# LedTester.net
KiCad netlist of a schematic drawn in EAGLE
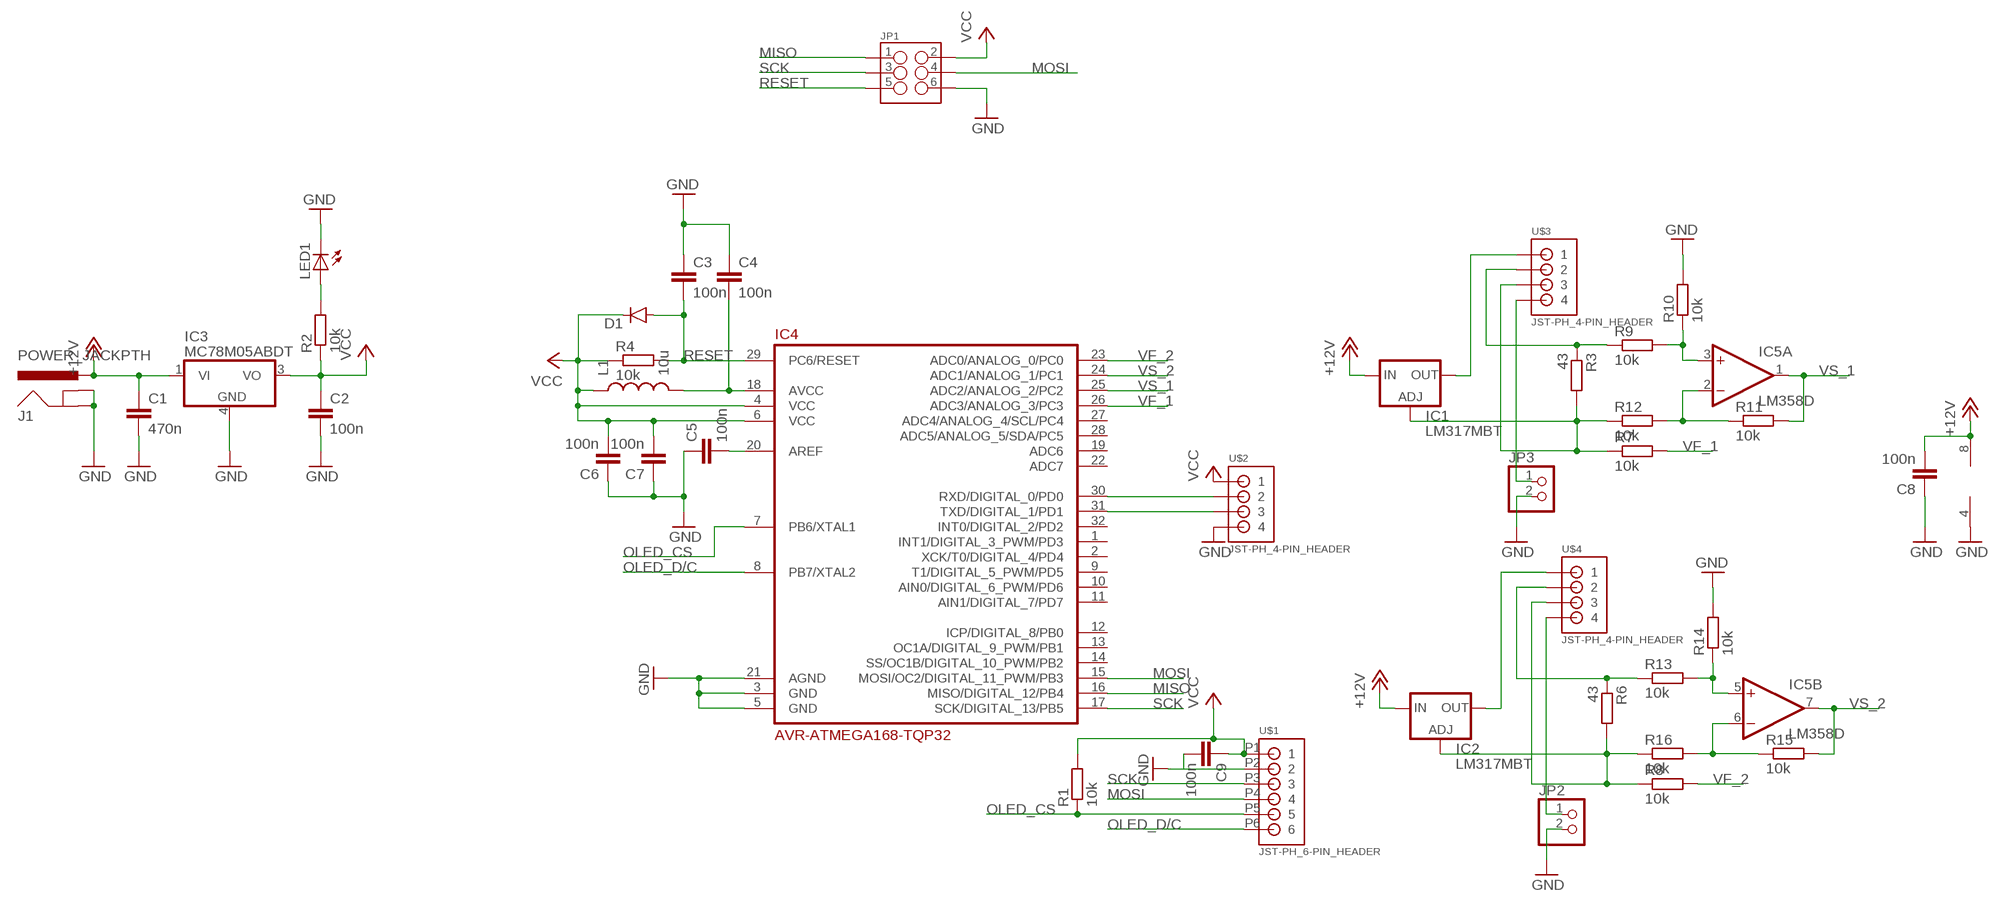
[diagram p0: schematic, sheet 1]

(export (version "E")
  (design (tool "Eeschema 10.0.6"))
  (components
    (comp (ref "C1")
      (value "470n")
      (footprint "eagle-import:C0603")
      (libsource (lib "eagle-import") (part "C-EUC0603"))
    )
    (comp (ref "C2")
      (value "100n")
      (footprint "eagle-import:C0603")
      (libsource (lib "eagle-import") (part "C-EUC0603"))
    )
    (comp (ref "C3")
      (value "100n")
      (footprint "eagle-import:C0603")
      (libsource (lib "eagle-import") (part "C-EUC0603"))
    )
    (comp (ref "C4")
      (value "100n")
      (footprint "eagle-import:C0603")
      (libsource (lib "eagle-import") (part "C-EUC0603"))
    )
    (comp (ref "C5")
      (value "100n")
      (footprint "eagle-import:C0603")
      (libsource (lib "eagle-import") (part "C-EUC0603"))
    )
    (comp (ref "C6")
      (value "100n")
      (footprint "eagle-import:C0603")
      (libsource (lib "eagle-import") (part "C-EUC0603"))
    )
    (comp (ref "C7")
      (value "100n")
      (footprint "eagle-import:C0603")
      (libsource (lib "eagle-import") (part "C-EUC0603"))
    )
    (comp (ref "C8")
      (value "100n")
      (footprint "eagle-import:C0603")
      (libsource (lib "eagle-import") (part "C-EUC0603"))
    )
    (comp (ref "C9")
      (value "100n")
      (footprint "eagle-import:C0603")
      (libsource (lib "eagle-import") (part "C-EUC0603"))
    )
    (comp (ref "D1")
      (value "DIODESOD")
      (footprint "eagle-import:SOD-323")
      (libsource (lib "eagle-import") (part "DIODESOD"))
    )
    (comp (ref "IC1")
      (value "LM317MBT")
      (footprint "eagle-import:TO220L1")
      (libsource (lib "eagle-import") (part "LM317?MBT"))
    )
    (comp (ref "IC2")
      (value "LM317MBT")
      (footprint "eagle-import:TO220L1")
      (libsource (lib "eagle-import") (part "LM317?MBT"))
    )
    (comp (ref "IC3")
      (value "MC78M05ABDT")
      (footprint "eagle-import:DPACK_3")
      (libsource (lib "eagle-import") (part "MC78M05ABDT"))
    )
    (comp (ref "IC4")
      (value "AVR-ATMEGA168-TQP32")
      (footprint "eagle-import:QFP32")
      (libsource (lib "eagle-import") (part "AVR-ATMEGA168-TQP32"))
    )
    (comp (ref "IC5")
      (value "LM358D")
      (footprint "eagle-import:SO08")
      (libsource (lib "eagle-import") (part "LM358D"))
    )
    (comp (ref "J1")
      (value "POWER_JACKPTH")
      (footprint "eagle-import:POWER_JACK_PTH")
      (libsource (lib "eagle-import") (part "POWER_JACKPTH"))
    )
    (comp (ref "JP1")
      (value "M03X2SHROUD")
      (footprint "eagle-import:2X3-SHROUDED")
      (libsource (lib "eagle-import") (part "M03X2SHROUD"))
    )
    (comp (ref "JP2")
      (value "PINHD-1X2")
      (footprint "eagle-import:1X02")
      (libsource (lib "eagle-import") (part "PINHD-1X2"))
    )
    (comp (ref "JP3")
      (value "PINHD-1X2")
      (footprint "eagle-import:1X02")
      (libsource (lib "eagle-import") (part "PINHD-1X2"))
    )
    (comp (ref "L1")
      (value "10u")
      (footprint "eagle-import:0603")
      (libsource (lib "eagle-import") (part "INDUCTOR0603"))
    )
    (comp (ref "LED1")
      (value "LEDCHIP-LED0603")
      (footprint "eagle-import:CHIP-LED0603")
      (libsource (lib "eagle-import") (part "LEDCHIP-LED0603"))
    )
    (comp (ref "R1")
      (value "10k")
      (footprint "eagle-import:R0603")
      (libsource (lib "eagle-import") (part "R-EU_R0603"))
    )
    (comp (ref "R2")
      (value "10k")
      (footprint "eagle-import:R0603")
      (libsource (lib "eagle-import") (part "R-EU_R0603"))
    )
    (comp (ref "R3")
      (value "43")
      (footprint "eagle-import:R0603")
      (libsource (lib "eagle-import") (part "R-EU_R0603"))
    )
    (comp (ref "R4")
      (value "10k")
      (footprint "eagle-import:R0603")
      (libsource (lib "eagle-import") (part "R-EU_R0603"))
    )
    (comp (ref "R6")
      (value "43")
      (footprint "eagle-import:R0603")
      (libsource (lib "eagle-import") (part "R-EU_R0603"))
    )
    (comp (ref "R7")
      (value "10k")
      (footprint "eagle-import:R0603")
      (libsource (lib "eagle-import") (part "R-EU_R0603"))
    )
    (comp (ref "R8")
      (value "10k")
      (footprint "eagle-import:R0603")
      (libsource (lib "eagle-import") (part "R-EU_R0603"))
    )
    (comp (ref "R9")
      (value "10k")
      (footprint "eagle-import:R0603")
      (libsource (lib "eagle-import") (part "R-EU_R0603"))
    )
    (comp (ref "R10")
      (value "10k")
      (footprint "eagle-import:R0603")
      (libsource (lib "eagle-import") (part "R-EU_R0603"))
    )
    (comp (ref "R11")
      (value "10k")
      (footprint "eagle-import:R0603")
      (libsource (lib "eagle-import") (part "R-EU_R0603"))
    )
    (comp (ref "R12")
      (value "10k")
      (footprint "eagle-import:R0603")
      (libsource (lib "eagle-import") (part "R-EU_R0603"))
    )
    (comp (ref "R13")
      (value "10k")
      (footprint "eagle-import:R0603")
      (libsource (lib "eagle-import") (part "R-EU_R0603"))
    )
    (comp (ref "R14")
      (value "10k")
      (footprint "eagle-import:R0603")
      (libsource (lib "eagle-import") (part "R-EU_R0603"))
    )
    (comp (ref "R15")
      (value "10k")
      (footprint "eagle-import:R0603")
      (libsource (lib "eagle-import") (part "R-EU_R0603"))
    )
    (comp (ref "R16")
      (value "10k")
      (footprint "eagle-import:R0603")
      (libsource (lib "eagle-import") (part "R-EU_R0603"))
    )
    (comp (ref "U$1")
      (value "JST-PH_6-PIN_HEADER")
      (footprint "eagle-import:JST_B6B-PH_HEADER")
      (libsource (lib "eagle-import") (part "JST-PH_6-PIN_HEADER"))
    )
    (comp (ref "U$2")
      (value "JST-PH_4-PIN_HEADER")
      (footprint "eagle-import:JST_B4B-PH_HEADER")
      (libsource (lib "eagle-import") (part "JST-PH_4-PIN_HEADER"))
    )
    (comp (ref "U$3")
      (value "JST-PH_4-PIN_HEADER")
      (footprint "eagle-import:JST_B4B-PH_HEADER")
      (libsource (lib "eagle-import") (part "JST-PH_4-PIN_HEADER"))
    )
    (comp (ref "U$4")
      (value "JST-PH_4-PIN_HEADER")
      (footprint "eagle-import:JST_B4B-PH_HEADER")
      (libsource (lib "eagle-import") (part "JST-PH_4-PIN_HEADER"))
    )
  )
  (nets
    (net (code "1") (name "+12V") (class "Default")
      (node (ref "C1") (pin "1") (pinfunction "1_1") (pintype "passive"))
      (node (ref "C8") (pin "2") (pinfunction "2_2") (pintype "passive"))
      (node (ref "IC1") (pin "3") (pinfunction "IN_3") (pintype "input"))
      (node (ref "IC2") (pin "3") (pinfunction "IN_3") (pintype "input"))
      (node (ref "IC3") (pin "1") (pinfunction "VI_1") (pintype "input"))
      (node (ref "IC5") (pin "8") (pinfunction "V+_8") (pintype "power_in"))
      (node (ref "J1") (pin "PWR") (pinfunction "PWR_PWR") (pintype "bidirectional"))
    )
    (net (code "2") (name "/MISO") (class "Default")
      (node (ref "IC4") (pin "16") (pinfunction "MISO/DIGITAL_12/PB4_16") (pintype "bidirectional"))
      (node (ref "JP1") (pin "1") (pinfunction "1_1") (pintype "bidirectional"))
    )
    (net (code "3") (name "/MOSI") (class "Default")
      (node (ref "IC4") (pin "15") (pinfunction "MOSI/OC2/DIGITAL_11_PWM/PB3_15") (pintype "bidirectional"))
      (node (ref "JP1") (pin "4") (pinfunction "4_4") (pintype "bidirectional"))
      (node (ref "U$1") (pin "P4") (pinfunction "4_P4") (pintype "bidirectional"))
    )
    (net (code "4") (name "/OLED_CS") (class "Default")
      (node (ref "IC4") (pin "7") (pinfunction "PB6/XTAL1_7") (pintype "bidirectional"))
      (node (ref "R1") (pin "1") (pinfunction "1_1") (pintype "passive"))
      (node (ref "U$1") (pin "P5") (pinfunction "5_P5") (pintype "bidirectional"))
    )
    (net (code "5") (name "/OLED_D{slash}C") (class "Default")
      (node (ref "IC4") (pin "8") (pinfunction "PB7/XTAL2_8") (pintype "bidirectional"))
      (node (ref "U$1") (pin "P6") (pinfunction "6_P6") (pintype "bidirectional"))
    )
    (net (code "6") (name "/RESET") (class "Default")
      (node (ref "C3") (pin "2") (pinfunction "2_2") (pintype "passive"))
      (node (ref "D1") (pin "A") (pinfunction "A_A") (pintype "passive"))
      (node (ref "IC4") (pin "29") (pinfunction "PC6/RESET_29") (pintype "bidirectional"))
      (node (ref "JP1") (pin "5") (pinfunction "5_5") (pintype "bidirectional"))
      (node (ref "R4") (pin "2") (pinfunction "2_2") (pintype "passive"))
    )
    (net (code "7") (name "/SCK") (class "Default")
      (node (ref "IC4") (pin "17") (pinfunction "SCK/DIGITAL_13/PB5_17") (pintype "bidirectional"))
      (node (ref "JP1") (pin "3") (pinfunction "3_3") (pintype "bidirectional"))
      (node (ref "U$1") (pin "P3") (pinfunction "3_P3") (pintype "bidirectional"))
    )
    (net (code "8") (name "/VF_1") (class "Default")
      (node (ref "IC4") (pin "26") (pinfunction "ADC3/ANALOG_3/PC3_26") (pintype "bidirectional"))
      (node (ref "R7") (pin "2") (pinfunction "2_2") (pintype "passive"))
    )
    (net (code "9") (name "/VF_2") (class "Default")
      (node (ref "IC4") (pin "23") (pinfunction "ADC0/ANALOG_0/PC0_23") (pintype "bidirectional"))
      (node (ref "R8") (pin "2") (pinfunction "2_2") (pintype "passive"))
    )
    (net (code "10") (name "/VS_1") (class "Default")
      (node (ref "IC4") (pin "25") (pinfunction "ADC2/ANALOG_2/PC2_25") (pintype "bidirectional"))
      (node (ref "IC5") (pin "1") (pinfunction "OUT_1") (pintype "output"))
      (node (ref "R11") (pin "2") (pinfunction "2_2") (pintype "passive"))
    )
    (net (code "11") (name "/VS_2") (class "Default")
      (node (ref "IC4") (pin "24") (pinfunction "ADC1/ANALOG_1/PC1_24") (pintype "bidirectional"))
      (node (ref "IC5") (pin "7") (pinfunction "OUT_7") (pintype "output"))
      (node (ref "R15") (pin "2") (pinfunction "2_2") (pintype "passive"))
    )
    (net (code "12") (name "GND") (class "Default")
      (node (ref "C1") (pin "2") (pinfunction "2_2") (pintype "passive"))
      (node (ref "C2") (pin "2") (pinfunction "2_2") (pintype "passive"))
      (node (ref "C3") (pin "1") (pinfunction "1_1") (pintype "passive"))
      (node (ref "C4") (pin "1") (pinfunction "1_1") (pintype "passive"))
      (node (ref "C5") (pin "1") (pinfunction "1_1") (pintype "passive"))
      (node (ref "C6") (pin "1") (pinfunction "1_1") (pintype "passive"))
      (node (ref "C7") (pin "1") (pinfunction "1_1") (pintype "passive"))
      (node (ref "C8") (pin "1") (pinfunction "1_1") (pintype "passive"))
      (node (ref "C9") (pin "2") (pinfunction "2_2") (pintype "passive"))
      (node (ref "IC3") (pin "4") (pinfunction "GND_4") (pintype "passive"))
      (node (ref "IC4") (pin "21") (pinfunction "AGND_21") (pintype "power_in"))
      (node (ref "IC4") (pin "3") (pinfunction "GND_3") (pintype "power_in"))
      (node (ref "IC4") (pin "5") (pinfunction "GND_5") (pintype "power_in"))
      (node (ref "IC5") (pin "4") (pinfunction "V-_4") (pintype "power_in"))
      (node (ref "J1") (pin "GND") (pinfunction "GND_GND") (pintype "bidirectional"))
      (node (ref "J1") (pin "GNDBREAK") (pinfunction "GNDBREAK_GNDBREAK") (pintype "bidirectional"))
      (node (ref "JP1") (pin "6") (pinfunction "6_6") (pintype "bidirectional"))
      (node (ref "JP2") (pin "2") (pinfunction "2_2") (pintype "passive"))
      (node (ref "JP3") (pin "2") (pinfunction "2_2") (pintype "passive"))
      (node (ref "LED1") (pin "C") (pinfunction "C_C") (pintype "passive"))
      (node (ref "R10") (pin "2") (pinfunction "2_2") (pintype "passive"))
      (node (ref "R14") (pin "2") (pinfunction "2_2") (pintype "passive"))
      (node (ref "U$1") (pin "P2") (pinfunction "2_P2") (pintype "bidirectional"))
      (node (ref "U$2") (pin "P4") (pinfunction "4_P4") (pintype "bidirectional"))
    )
    (net (code "13") (name "Net-(IC1-ADJ)") (class "Default")
      (node (ref "IC1") (pin "1") (pinfunction "ADJ_1") (pintype "input"))
      (node (ref "R12") (pin "1") (pinfunction "1_1") (pintype "passive"))
      (node (ref "R3") (pin "2") (pinfunction "2_2") (pintype "passive"))
      (node (ref "R7") (pin "1") (pinfunction "1_1") (pintype "passive"))
      (node (ref "U$3") (pin "P3") (pinfunction "3_P3") (pintype "bidirectional"))
    )
    (net (code "14") (name "Net-(IC1-OUT)") (class "Default")
      (node (ref "IC1") (pin "2") (pinfunction "OUT_2") (pintype "passive"))
      (node (ref "U$3") (pin "P1") (pinfunction "1_P1") (pintype "bidirectional"))
    )
    (net (code "15") (name "Net-(IC2-ADJ)") (class "Default")
      (node (ref "IC2") (pin "1") (pinfunction "ADJ_1") (pintype "input"))
      (node (ref "R16") (pin "1") (pinfunction "1_1") (pintype "passive"))
      (node (ref "R6") (pin "2") (pinfunction "2_2") (pintype "passive"))
      (node (ref "R8") (pin "1") (pinfunction "1_1") (pintype "passive"))
      (node (ref "U$4") (pin "P3") (pinfunction "3_P3") (pintype "bidirectional"))
    )
    (net (code "16") (name "Net-(IC2-OUT)") (class "Default")
      (node (ref "IC2") (pin "2") (pinfunction "OUT_2") (pintype "passive"))
      (node (ref "U$4") (pin "P1") (pinfunction "1_P1") (pintype "bidirectional"))
    )
    (net (code "17") (name "Net-(IC4-AREF)") (class "Default")
      (node (ref "C5") (pin "2") (pinfunction "2_2") (pintype "passive"))
      (node (ref "IC4") (pin "20") (pinfunction "AREF_20") (pintype "bidirectional"))
    )
    (net (code "18") (name "Net-(IC4-AVCC)") (class "Default")
      (node (ref "C4") (pin "2") (pinfunction "2_2") (pintype "passive"))
      (node (ref "IC4") (pin "18") (pinfunction "AVCC_18") (pintype "power_in"))
      (node (ref "L1") (pin "2") (pinfunction "2_2") (pintype "passive"))
    )
    (net (code "19") (name "Net-(IC4-RXD{slash}DIGITAL_0{slash}PD0)") (class "Default")
      (node (ref "IC4") (pin "30") (pinfunction "RXD/DIGITAL_0/PD0_30") (pintype "bidirectional"))
      (node (ref "U$2") (pin "P2") (pinfunction "2_P2") (pintype "bidirectional"))
    )
    (net (code "20") (name "Net-(IC4-TXD{slash}DIGITAL_1{slash}PD1)") (class "Default")
      (node (ref "IC4") (pin "31") (pinfunction "TXD/DIGITAL_1/PD1_31") (pintype "bidirectional"))
      (node (ref "U$2") (pin "P3") (pinfunction "3_P3") (pintype "bidirectional"))
    )
    (net (code "21") (name "Net-(IC5A-+IN)") (class "Default")
      (node (ref "IC5") (pin "3") (pinfunction "+IN_3") (pintype "input"))
      (node (ref "R10") (pin "1") (pinfunction "1_1") (pintype "passive"))
      (node (ref "R9") (pin "2") (pinfunction "2_2") (pintype "passive"))
    )
    (net (code "22") (name "Net-(IC5A--IN)") (class "Default")
      (node (ref "IC5") (pin "2") (pinfunction "-IN_2") (pintype "input"))
      (node (ref "R11") (pin "1") (pinfunction "1_1") (pintype "passive"))
      (node (ref "R12") (pin "2") (pinfunction "2_2") (pintype "passive"))
    )
    (net (code "23") (name "Net-(IC5B-+IN)") (class "Default")
      (node (ref "IC5") (pin "5") (pinfunction "+IN_5") (pintype "input"))
      (node (ref "R13") (pin "2") (pinfunction "2_2") (pintype "passive"))
      (node (ref "R14") (pin "1") (pinfunction "1_1") (pintype "passive"))
    )
    (net (code "24") (name "Net-(IC5B--IN)") (class "Default")
      (node (ref "IC5") (pin "6") (pinfunction "-IN_6") (pintype "input"))
      (node (ref "R15") (pin "1") (pinfunction "1_1") (pintype "passive"))
      (node (ref "R16") (pin "2") (pinfunction "2_2") (pintype "passive"))
    )
    (net (code "25") (name "Net-(LED1-PadA)") (class "Default")
      (node (ref "LED1") (pin "A") (pinfunction "A_A") (pintype "passive"))
      (node (ref "R2") (pin "2") (pinfunction "2_2") (pintype "passive"))
    )
    (net (code "26") (name "Net-(U$3-2)") (class "Default")
      (node (ref "R3") (pin "1") (pinfunction "1_1") (pintype "passive"))
      (node (ref "R9") (pin "1") (pinfunction "1_1") (pintype "passive"))
      (node (ref "U$3") (pin "P2") (pinfunction "2_P2") (pintype "bidirectional"))
    )
    (net (code "27") (name "Net-(U$3-4)") (class "Default")
      (node (ref "JP3") (pin "1") (pinfunction "1_1") (pintype "passive"))
      (node (ref "U$3") (pin "P4") (pinfunction "4_P4") (pintype "bidirectional"))
    )
    (net (code "28") (name "Net-(U$4-2)") (class "Default")
      (node (ref "R13") (pin "1") (pinfunction "1_1") (pintype "passive"))
      (node (ref "R6") (pin "1") (pinfunction "1_1") (pintype "passive"))
      (node (ref "U$4") (pin "P2") (pinfunction "2_P2") (pintype "bidirectional"))
    )
    (net (code "29") (name "Net-(U$4-4)") (class "Default")
      (node (ref "JP2") (pin "1") (pinfunction "1_1") (pintype "passive"))
      (node (ref "U$4") (pin "P4") (pinfunction "4_P4") (pintype "bidirectional"))
    )
    (net (code "30") (name "VCC") (class "Default")
      (node (ref "C2") (pin "1") (pinfunction "1_1") (pintype "passive"))
      (node (ref "C6") (pin "2") (pinfunction "2_2") (pintype "passive"))
      (node (ref "C7") (pin "2") (pinfunction "2_2") (pintype "passive"))
      (node (ref "C9") (pin "1") (pinfunction "1_1") (pintype "passive"))
      (node (ref "D1") (pin "C") (pinfunction "C_C") (pintype "passive"))
      (node (ref "IC3") (pin "3") (pinfunction "VO_3") (pintype "passive"))
      (node (ref "IC4") (pin "4") (pinfunction "VCC_4") (pintype "power_in"))
      (node (ref "IC4") (pin "6") (pinfunction "VCC_6") (pintype "power_in"))
      (node (ref "JP1") (pin "2") (pinfunction "2_2") (pintype "bidirectional"))
      (node (ref "L1") (pin "1") (pinfunction "1_1") (pintype "passive"))
      (node (ref "R1") (pin "2") (pinfunction "2_2") (pintype "passive"))
      (node (ref "R2") (pin "1") (pinfunction "1_1") (pintype "passive"))
      (node (ref "R4") (pin "1") (pinfunction "1_1") (pintype "passive"))
      (node (ref "U$1") (pin "P1") (pinfunction "1_P1") (pintype "bidirectional"))
      (node (ref "U$2") (pin "P1") (pinfunction "1_P1") (pintype "bidirectional"))
    )
    (net (code "31") (name "unconnected-(IC4-ADC4{slash}ANALOG_4{slash}SCL{slash}PC4-Pad27)") (class "Default")
      (node (ref "IC4") (pin "27") (pinfunction "ADC4/ANALOG_4/SCL/PC4_27") (pintype "bidirectional"))
    )
    (net (code "32") (name "unconnected-(IC4-ADC5{slash}ANALOG_5{slash}SDA{slash}PC5-Pad28)") (class "Default")
      (node (ref "IC4") (pin "28") (pinfunction "ADC5/ANALOG_5/SDA/PC5_28") (pintype "bidirectional"))
    )
    (net (code "33") (name "unconnected-(IC4-ADC6-Pad19)") (class "Default")
      (node (ref "IC4") (pin "19") (pinfunction "ADC6_19") (pintype "bidirectional"))
    )
    (net (code "34") (name "unconnected-(IC4-ADC7-Pad22)") (class "Default")
      (node (ref "IC4") (pin "22") (pinfunction "ADC7_22") (pintype "bidirectional"))
    )
    (net (code "35") (name "unconnected-(IC4-AIN0{slash}DIGITAL_6_PWM{slash}PD6-Pad10)") (class "Default")
      (node (ref "IC4") (pin "10") (pinfunction "AIN0/DIGITAL_6_PWM/PD6_10") (pintype "bidirectional"))
    )
    (net (code "36") (name "unconnected-(IC4-AIN1{slash}DIGITAL_7{slash}PD7-Pad11)") (class "Default")
      (node (ref "IC4") (pin "11") (pinfunction "AIN1/DIGITAL_7/PD7_11") (pintype "bidirectional"))
    )
    (net (code "37") (name "unconnected-(IC4-ICP{slash}DIGITAL_8{slash}PB0-Pad12)") (class "Default")
      (node (ref "IC4") (pin "12") (pinfunction "ICP/DIGITAL_8/PB0_12") (pintype "bidirectional"))
    )
    (net (code "38") (name "unconnected-(IC4-INT0{slash}DIGITAL_2{slash}PD2-Pad32)") (class "Default")
      (node (ref "IC4") (pin "32") (pinfunction "INT0/DIGITAL_2/PD2_32") (pintype "bidirectional"))
    )
    (net (code "39") (name "unconnected-(IC4-INT1{slash}DIGITAL_3_PWM{slash}PD3-Pad1)") (class "Default")
      (node (ref "IC4") (pin "1") (pinfunction "INT1/DIGITAL_3_PWM/PD3_1") (pintype "bidirectional"))
    )
    (net (code "40") (name "unconnected-(IC4-OC1A{slash}DIGITAL_9_PWM{slash}PB1-Pad13)") (class "Default")
      (node (ref "IC4") (pin "13") (pinfunction "OC1A/DIGITAL_9_PWM/PB1_13") (pintype "bidirectional"))
    )
    (net (code "41") (name "unconnected-(IC4-SS{slash}OC1B{slash}DIGITAL_10_PWM{slash}PB2-Pad14)") (class "Default")
      (node (ref "IC4") (pin "14") (pinfunction "SS/OC1B/DIGITAL_10_PWM/PB2_14") (pintype "bidirectional"))
    )
    (net (code "42") (name "unconnected-(IC4-T1{slash}DIGITAL_5_PWM{slash}PD5-Pad9)") (class "Default")
      (node (ref "IC4") (pin "9") (pinfunction "T1/DIGITAL_5_PWM/PD5_9") (pintype "bidirectional"))
    )
    (net (code "43") (name "unconnected-(IC4-XCK{slash}T0{slash}DIGITAL_4{slash}PD4-Pad2)") (class "Default")
      (node (ref "IC4") (pin "2") (pinfunction "XCK/T0/DIGITAL_4/PD4_2") (pintype "bidirectional"))
    )
  )
)
